# fsr_endstop.net
KiCad netlist of a schematic drawn in EAGLE
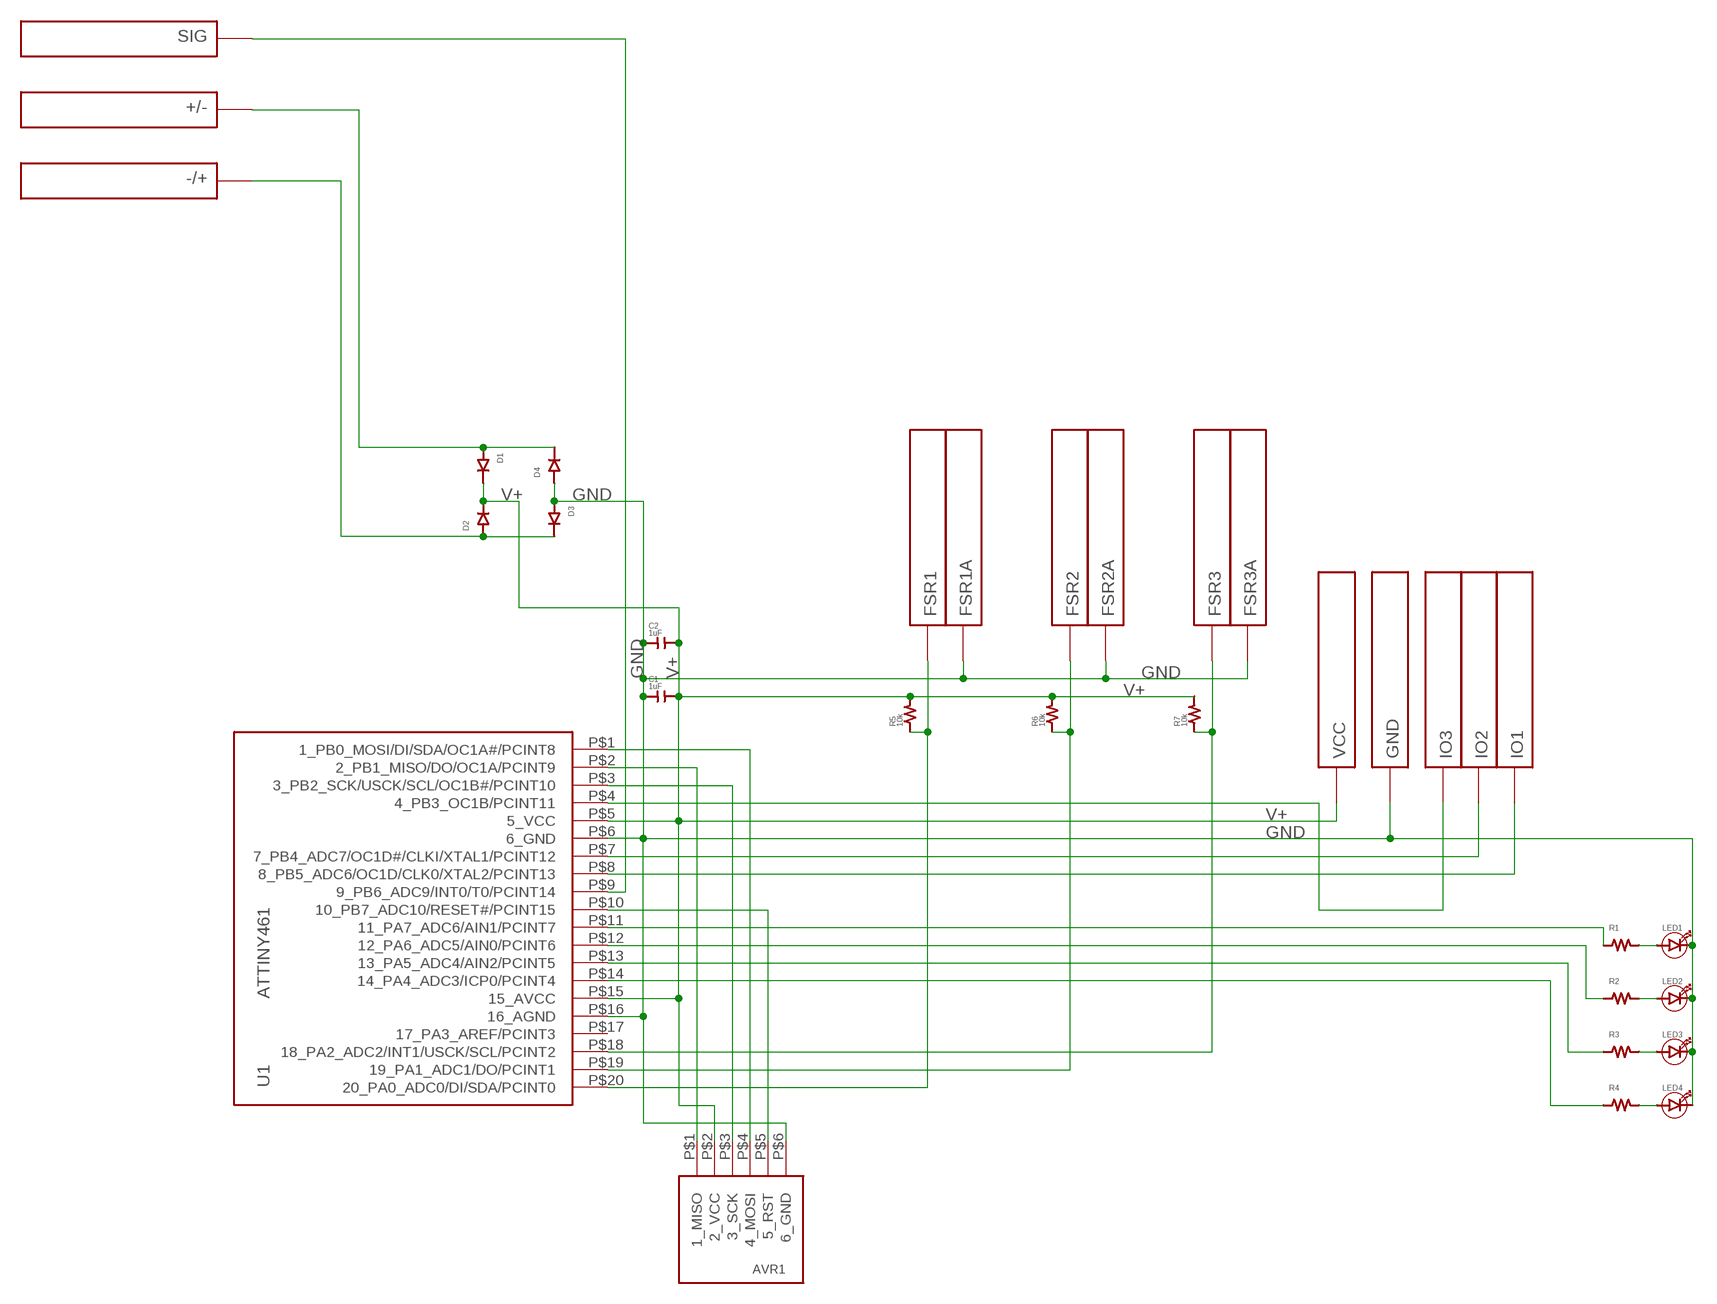
[diagram p0: schematic, sheet 1]

(export (version "E")
  (design (tool "Eeschema 10.0.6"))
  (components
    (comp (ref "+/-")
      (value "PIN1.2MM")
      (footprint "eagle-import:PIN_1.2MM")
      (libsource (lib "eagle-import") (part "PIN1.2MM"))
    )
    (comp (ref "-/+")
      (value "PIN1.2MM")
      (footprint "eagle-import:PIN_1.2MM")
      (libsource (lib "eagle-import") (part "PIN1.2MM"))
    )
    (comp (ref "AVR1")
      (value "AVR6")
      (footprint "eagle-import:AVR6")
      (libsource (lib "eagle-import") (part "AVR6"))
    )
    (comp (ref "C1")
      (value "1uF")
      (footprint "eagle-import:0603")
      (libsource (lib "eagle-import") (part "CAP0603"))
    )
    (comp (ref "C2")
      (value "1uF")
      (footprint "eagle-import:0603")
      (libsource (lib "eagle-import") (part "CAP0603"))
    )
    (comp (ref "D1")
      (value "DIODE0603")
      (footprint "eagle-import:0603_DIODE")
      (libsource (lib "eagle-import") (part "DIODE0603"))
    )
    (comp (ref "D2")
      (value "DIODE0603")
      (footprint "eagle-import:0603_DIODE")
      (libsource (lib "eagle-import") (part "DIODE0603"))
    )
    (comp (ref "D3")
      (value "DIODE0603")
      (footprint "eagle-import:0603_DIODE")
      (libsource (lib "eagle-import") (part "DIODE0603"))
    )
    (comp (ref "D4")
      (value "DIODE0603")
      (footprint "eagle-import:0603_DIODE")
      (libsource (lib "eagle-import") (part "DIODE0603"))
    )
    (comp (ref "FSR1")
      (value "PIN1.2MM")
      (footprint "eagle-import:PIN_1.2MM")
      (libsource (lib "eagle-import") (part "PIN1.2MM"))
    )
    (comp (ref "FSR1A")
      (value "PIN1.2MM")
      (footprint "eagle-import:PIN_1.2MM")
      (libsource (lib "eagle-import") (part "PIN1.2MM"))
    )
    (comp (ref "FSR2")
      (value "PIN1.2MM")
      (footprint "eagle-import:PIN_1.2MM")
      (libsource (lib "eagle-import") (part "PIN1.2MM"))
    )
    (comp (ref "FSR2A")
      (value "PIN1.2MM")
      (footprint "eagle-import:PIN_1.2MM")
      (libsource (lib "eagle-import") (part "PIN1.2MM"))
    )
    (comp (ref "FSR3")
      (value "PIN1.2MM")
      (footprint "eagle-import:PIN_1.2MM")
      (libsource (lib "eagle-import") (part "PIN1.2MM"))
    )
    (comp (ref "FSR3A")
      (value "PIN1.2MM")
      (footprint "eagle-import:PIN_1.2MM")
      (libsource (lib "eagle-import") (part "PIN1.2MM"))
    )
    (comp (ref "GND")
      (value "PIN1.2MM")
      (footprint "eagle-import:PIN_1.2MM")
      (libsource (lib "eagle-import") (part "PIN1.2MM"))
    )
    (comp (ref "IO1")
      (value "PIN1.2MM")
      (footprint "eagle-import:PIN_1.2MM")
      (libsource (lib "eagle-import") (part "PIN1.2MM"))
    )
    (comp (ref "IO2")
      (value "PIN1.2MM")
      (footprint "eagle-import:PIN_1.2MM")
      (libsource (lib "eagle-import") (part "PIN1.2MM"))
    )
    (comp (ref "IO3")
      (value "PIN1.2MM")
      (footprint "eagle-import:PIN_1.2MM")
      (libsource (lib "eagle-import") (part "PIN1.2MM"))
    )
    (comp (ref "LED1")
      (value "LED0603")
      (footprint "eagle-import:0603_DIODE")
      (libsource (lib "eagle-import") (part "LED0603"))
    )
    (comp (ref "LED2")
      (value "LED0603")
      (footprint "eagle-import:0603_DIODE")
      (libsource (lib "eagle-import") (part "LED0603"))
    )
    (comp (ref "LED3")
      (value "LED0603")
      (footprint "eagle-import:0603_DIODE")
      (libsource (lib "eagle-import") (part "LED0603"))
    )
    (comp (ref "LED4")
      (value "LED0603")
      (footprint "eagle-import:0603_DIODE")
      (libsource (lib "eagle-import") (part "LED0603"))
    )
    (comp (ref "R1")
      (value "RES0603")
      (footprint "eagle-import:0603")
      (libsource (lib "eagle-import") (part "RES0603"))
    )
    (comp (ref "R2")
      (value "RES0603")
      (footprint "eagle-import:0603")
      (libsource (lib "eagle-import") (part "RES0603"))
    )
    (comp (ref "R3")
      (value "RES0603")
      (footprint "eagle-import:0603")
      (libsource (lib "eagle-import") (part "RES0603"))
    )
    (comp (ref "R4")
      (value "RES0603")
      (footprint "eagle-import:0603")
      (libsource (lib "eagle-import") (part "RES0603"))
    )
    (comp (ref "R5")
      (value "10k")
      (footprint "eagle-import:0603")
      (libsource (lib "eagle-import") (part "RES0603"))
    )
    (comp (ref "R6")
      (value "10k")
      (footprint "eagle-import:0603")
      (libsource (lib "eagle-import") (part "RES0603"))
    )
    (comp (ref "R7")
      (value "10k")
      (footprint "eagle-import:0603")
      (libsource (lib "eagle-import") (part "RES0603"))
    )
    (comp (ref "SIG")
      (value "PIN1.2MM")
      (footprint "eagle-import:PIN_1.2MM")
      (libsource (lib "eagle-import") (part "PIN1.2MM"))
    )
    (comp (ref "U1")
      (value "ATTINY461")
      (footprint "eagle-import:SOIC-20")
      (libsource (lib "eagle-import") (part "ATTINY461"))
    )
    (comp (ref "VCC")
      (value "PIN1.2MM")
      (footprint "eagle-import:PIN_1.2MM")
      (libsource (lib "eagle-import") (part "PIN1.2MM"))
    )
  )
  (nets
    (net (code "1") (name "/GND") (class "Default")
      (node (ref "AVR1") (pin "P$6") (pinfunction "6_GND_P$6") (pintype "bidirectional"))
      (node (ref "C1") (pin "1") (pinfunction "P$1_1") (pintype "bidirectional"))
      (node (ref "C2") (pin "1") (pinfunction "P$1_1") (pintype "bidirectional"))
      (node (ref "D3") (pin "+") (pinfunction "+_+") (pintype "bidirectional"))
      (node (ref "D4") (pin "+") (pinfunction "+_+") (pintype "bidirectional"))
      (node (ref "FSR1A") (pin "P$1") (pinfunction "P$1_P$1") (pintype "bidirectional"))
      (node (ref "FSR2A") (pin "P$1") (pinfunction "P$1_P$1") (pintype "bidirectional"))
      (node (ref "FSR3A") (pin "P$1") (pinfunction "P$1_P$1") (pintype "bidirectional"))
      (node (ref "GND") (pin "P$1") (pinfunction "P$1_P$1") (pintype "bidirectional"))
      (node (ref "LED1") (pin "-") (pinfunction "-_-") (pintype "bidirectional"))
      (node (ref "LED2") (pin "-") (pinfunction "-_-") (pintype "bidirectional"))
      (node (ref "LED3") (pin "-") (pinfunction "-_-") (pintype "bidirectional"))
      (node (ref "LED4") (pin "-") (pinfunction "-_-") (pintype "bidirectional"))
      (node (ref "U1") (pin "P$16") (pinfunction "16_AGND_P$16") (pintype "bidirectional"))
      (node (ref "U1") (pin "P$6") (pinfunction "6_GND_P$6") (pintype "bidirectional"))
    )
    (net (code "2") (name "/V+") (class "Default")
      (node (ref "AVR1") (pin "P$2") (pinfunction "2_VCC_P$2") (pintype "bidirectional"))
      (node (ref "C1") (pin "2") (pinfunction "P$2_2") (pintype "bidirectional"))
      (node (ref "C2") (pin "2") (pinfunction "P$2_2") (pintype "bidirectional"))
      (node (ref "D1") (pin "-") (pinfunction "-_-") (pintype "bidirectional"))
      (node (ref "D2") (pin "-") (pinfunction "-_-") (pintype "bidirectional"))
      (node (ref "R5") (pin "2") (pinfunction "P$2_2") (pintype "bidirectional"))
      (node (ref "R6") (pin "2") (pinfunction "P$2_2") (pintype "bidirectional"))
      (node (ref "R7") (pin "2") (pinfunction "P$2_2") (pintype "bidirectional"))
      (node (ref "U1") (pin "P$15") (pinfunction "15_AVCC_P$15") (pintype "bidirectional"))
      (node (ref "U1") (pin "P$5") (pinfunction "5_VCC_P$5") (pintype "bidirectional"))
      (node (ref "VCC") (pin "P$1") (pinfunction "P$1_P$1") (pintype "bidirectional"))
    )
    (net (code "3") (name "Net-(+/--PadP$1)") (class "Default")
      (node (ref "+/-") (pin "P$1") (pinfunction "P$1_P$1") (pintype "bidirectional"))
      (node (ref "D1") (pin "+") (pinfunction "+_+") (pintype "bidirectional"))
      (node (ref "D4") (pin "-") (pinfunction "-_-") (pintype "bidirectional"))
    )
    (net (code "4") (name "Net-(-/+-PadP$1)") (class "Default")
      (node (ref "-/+") (pin "P$1") (pinfunction "P$1_P$1") (pintype "bidirectional"))
      (node (ref "D2") (pin "+") (pinfunction "+_+") (pintype "bidirectional"))
      (node (ref "D3") (pin "-") (pinfunction "-_-") (pintype "bidirectional"))
    )
    (net (code "5") (name "Net-(AVR1-1_MISO)") (class "Default")
      (node (ref "AVR1") (pin "P$1") (pinfunction "1_MISO_P$1") (pintype "bidirectional"))
      (node (ref "U1") (pin "P$2") (pinfunction "2_PB1_MISO/DO/OC1A/PCINT9_P$2") (pintype "bidirectional"))
    )
    (net (code "6") (name "Net-(AVR1-3_SCK)") (class "Default")
      (node (ref "AVR1") (pin "P$3") (pinfunction "3_SCK_P$3") (pintype "bidirectional"))
      (node (ref "U1") (pin "P$3") (pinfunction "3_PB2_SCK/USCK/SCL/OC1B#/PCINT10_P$3") (pintype "bidirectional"))
    )
    (net (code "7") (name "Net-(AVR1-4_MOSI)") (class "Default")
      (node (ref "AVR1") (pin "P$4") (pinfunction "4_MOSI_P$4") (pintype "bidirectional"))
      (node (ref "U1") (pin "P$1") (pinfunction "1_PB0_MOSI/DI/SDA/OC1A#/PCINT8_P$1") (pintype "bidirectional"))
    )
    (net (code "8") (name "Net-(AVR1-5_RST)") (class "Default")
      (node (ref "AVR1") (pin "P$5") (pinfunction "5_RST_P$5") (pintype "bidirectional"))
      (node (ref "U1") (pin "P$10") (pinfunction "10_PB7_ADC10/RESET#/PCINT15_P$10") (pintype "bidirectional"))
    )
    (net (code "9") (name "Net-(R1-P$1)") (class "Default")
      (node (ref "R1") (pin "1") (pinfunction "P$1_1") (pintype "bidirectional"))
      (node (ref "U1") (pin "P$11") (pinfunction "11_PA7_ADC6/AIN1/PCINT7_P$11") (pintype "bidirectional"))
    )
    (net (code "10") (name "Net-(R1-P$2)") (class "Default")
      (node (ref "LED1") (pin "+") (pinfunction "+_+") (pintype "bidirectional"))
      (node (ref "R1") (pin "2") (pinfunction "P$2_2") (pintype "bidirectional"))
    )
    (net (code "11") (name "Net-(R2-P$1)") (class "Default")
      (node (ref "R2") (pin "1") (pinfunction "P$1_1") (pintype "bidirectional"))
      (node (ref "U1") (pin "P$12") (pinfunction "12_PA6_ADC5/AIN0/PCINT6_P$12") (pintype "bidirectional"))
    )
    (net (code "12") (name "Net-(R2-P$2)") (class "Default")
      (node (ref "LED2") (pin "+") (pinfunction "+_+") (pintype "bidirectional"))
      (node (ref "R2") (pin "2") (pinfunction "P$2_2") (pintype "bidirectional"))
    )
    (net (code "13") (name "Net-(R3-P$1)") (class "Default")
      (node (ref "R3") (pin "1") (pinfunction "P$1_1") (pintype "bidirectional"))
      (node (ref "U1") (pin "P$13") (pinfunction "13_PA5_ADC4/AIN2/PCINT5_P$13") (pintype "bidirectional"))
    )
    (net (code "14") (name "Net-(R3-P$2)") (class "Default")
      (node (ref "LED3") (pin "+") (pinfunction "+_+") (pintype "bidirectional"))
      (node (ref "R3") (pin "2") (pinfunction "P$2_2") (pintype "bidirectional"))
    )
    (net (code "15") (name "Net-(R4-P$1)") (class "Default")
      (node (ref "R4") (pin "1") (pinfunction "P$1_1") (pintype "bidirectional"))
      (node (ref "U1") (pin "P$14") (pinfunction "14_PA4_ADC3/ICP0/PCINT4_P$14") (pintype "bidirectional"))
    )
    (net (code "16") (name "Net-(R4-P$2)") (class "Default")
      (node (ref "LED4") (pin "+") (pinfunction "+_+") (pintype "bidirectional"))
      (node (ref "R4") (pin "2") (pinfunction "P$2_2") (pintype "bidirectional"))
    )
    (net (code "17") (name "Net-(R5-P$1)") (class "Default")
      (node (ref "FSR1") (pin "P$1") (pinfunction "P$1_P$1") (pintype "bidirectional"))
      (node (ref "R5") (pin "1") (pinfunction "P$1_1") (pintype "bidirectional"))
      (node (ref "U1") (pin "P$20") (pinfunction "20_PA0_ADC0/DI/SDA/PCINT0_P$20") (pintype "bidirectional"))
    )
    (net (code "18") (name "Net-(R6-P$1)") (class "Default")
      (node (ref "FSR2") (pin "P$1") (pinfunction "P$1_P$1") (pintype "bidirectional"))
      (node (ref "R6") (pin "1") (pinfunction "P$1_1") (pintype "bidirectional"))
      (node (ref "U1") (pin "P$19") (pinfunction "19_PA1_ADC1/DO/PCINT1_P$19") (pintype "bidirectional"))
    )
    (net (code "19") (name "Net-(R7-P$1)") (class "Default")
      (node (ref "FSR3") (pin "P$1") (pinfunction "P$1_P$1") (pintype "bidirectional"))
      (node (ref "R7") (pin "1") (pinfunction "P$1_1") (pintype "bidirectional"))
      (node (ref "U1") (pin "P$18") (pinfunction "18_PA2_ADC2/INT1/USCK/SCL/PCINT2_P$18") (pintype "bidirectional"))
    )
    (net (code "20") (name "Net-(U1-4_PB3_OC1B{slash}PCINT11)") (class "Default")
      (node (ref "IO3") (pin "P$1") (pinfunction "P$1_P$1") (pintype "bidirectional"))
      (node (ref "U1") (pin "P$4") (pinfunction "4_PB3_OC1B/PCINT11_P$4") (pintype "bidirectional"))
    )
    (net (code "21") (name "Net-(U1-7_PB4_ADC7{slash}OC1D#{slash}CLKI{slash}XTAL1{slash}PCINT12)") (class "Default")
      (node (ref "IO2") (pin "P$1") (pinfunction "P$1_P$1") (pintype "bidirectional"))
      (node (ref "U1") (pin "P$7") (pinfunction "7_PB4_ADC7/OC1D#/CLKI/XTAL1/PCINT12_P$7") (pintype "bidirectional"))
    )
    (net (code "22") (name "Net-(U1-8_PB5_ADC6{slash}OC1D{slash}CLK0{slash}XTAL2{slash}PCINT13)") (class "Default")
      (node (ref "IO1") (pin "P$1") (pinfunction "P$1_P$1") (pintype "bidirectional"))
      (node (ref "U1") (pin "P$8") (pinfunction "8_PB5_ADC6/OC1D/CLK0/XTAL2/PCINT13_P$8") (pintype "bidirectional"))
    )
    (net (code "23") (name "Net-(U1-9_PB6_ADC9{slash}INT0{slash}T0{slash}PCINT14)") (class "Default")
      (node (ref "SIG") (pin "P$1") (pinfunction "P$1_P$1") (pintype "bidirectional"))
      (node (ref "U1") (pin "P$9") (pinfunction "9_PB6_ADC9/INT0/T0/PCINT14_P$9") (pintype "bidirectional"))
    )
    (net (code "24") (name "unconnected-(U1-17_PA3_AREF{slash}PCINT3-PadP$17)") (class "Default")
      (node (ref "U1") (pin "P$17") (pinfunction "17_PA3_AREF/PCINT3_P$17") (pintype "bidirectional"))
    )
  )
)
